# A4-B.net
KiCad netlist of a schematic drawn in Altium Designer
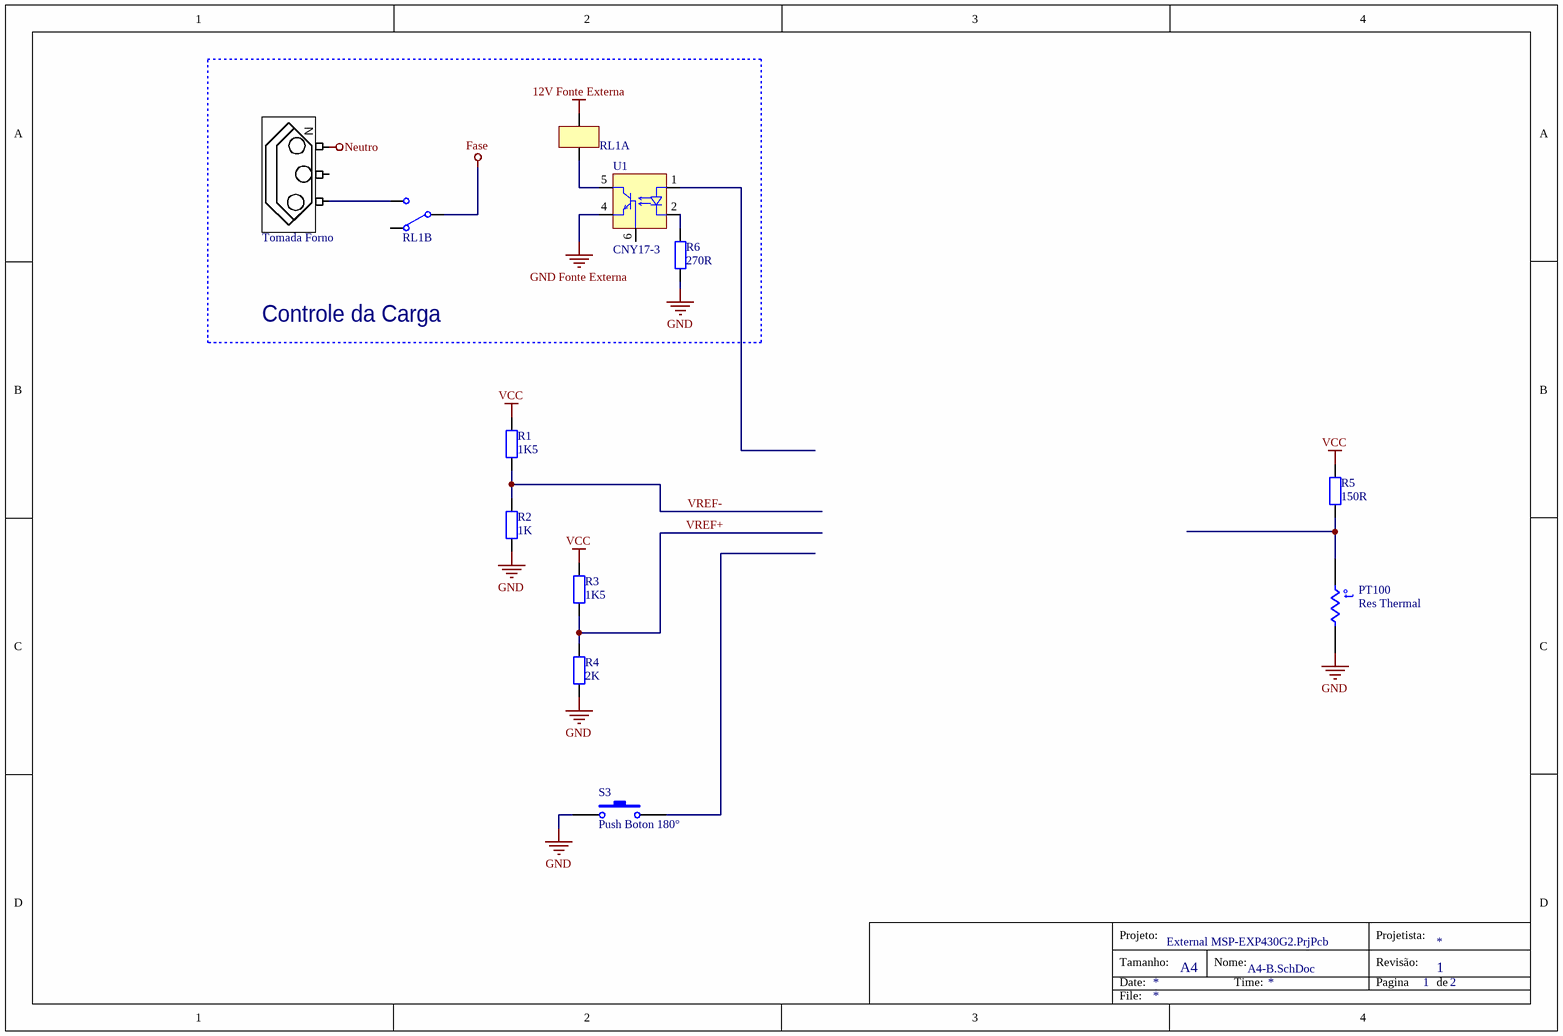
[diagram p0: A4-B.SchDoc]

(export (version "E")
  (design (tool "Eeschema 10.0.6"))
  (components
    (comp (ref "PT100")
      (value "Res Thermal")
      (footprint "6-0805_N")
      (description "Thermistor")
      (fields (field (name "PUBLISHER") "Altium Limited"))
      (libsource (lib "Miscellaneous Devices") (part "Res Thermal"))
    )
    (comp (ref "R1")
      (value "1K5")
      (footprint "Resistor 1/8")
      (description "Resistor")
      (fields (field (name "Comment") "Res 1K5") (field (name "PUBLISHER") "Altium Limited"))
      (libsource (lib "almox Gaia") (part "Res 1K5"))
    )
    (comp (ref "R2")
      (value "1K")
      (footprint "Resistor 1/8")
      (description "Resistor")
      (fields (field (name "Comment") "Res 1K") (field (name "PUBLISHER") "Altium Limited"))
      (libsource (lib "almox Gaia") (part "Res 1K"))
    )
    (comp (ref "R3")
      (value "1K5")
      (footprint "Resistor 1/8")
      (description "Resistor")
      (fields (field (name "Comment") "Res 1K5") (field (name "PUBLISHER") "Altium Limited"))
      (libsource (lib "almox Gaia") (part "Res 1K5"))
    )
    (comp (ref "R4")
      (value "2K")
      (footprint "Resistor 1/8")
      (description "Resistor")
      (fields (field (name "Comment") "Res 2K") (field (name "PUBLISHER") "Altium Limited"))
      (libsource (lib "almox Gaia") (part "Res 2K2"))
    )
    (comp (ref "R5")
      (value "150R")
      (footprint "Resistor 1/8")
      (description "Resistor")
      (fields (field (name "Comment") "Res 150R") (field (name "PUBLISHER") "Altium Limited"))
      (libsource (lib "almox Gaia") (part "Res 180R"))
    )
    (comp (ref "R6")
      (value "270R")
      (footprint "Resistor 1/8")
      (description "Resistor")
      (fields (field (name "Comment") "Res 270R") (field (name "PUBLISHER") "Altium Limited"))
      (libsource (lib "almox Gaia") (part "Res 270R"))
    )
    (comp (ref "RL1")
      (value "RELE 1NA 1NF")
      (footprint "rele SRA")
      (description "Relay")
      (fields (field (name "MANUFACTURER") "Metaltex") (field (name "PUBLISHER") "Gaia Component"))
      (libsource (lib "almox Gaia") (part "RELE 1NA 1NF"))
    )
    (comp (ref "S3")
      (value "Push Boton 180°")
      (footprint "PushButton - small - 2")
      (description "Switch")
      (fields (field (name "PUBLISHER") "Altium Limited"))
      (libsource (lib "almox Gaia") (part "Push Boton 180°"))
    )
    (comp (ref "Tomada Forno")
      (value "TOMADA AC RETA")
      (footprint "EX-1401")
      (description "TOMADA AC")
      (fields (field (name "PUBLISHER") "Altium Limited"))
      (libsource (lib "almox Gaia") (part "TOMADA AC RETA"))
    )
    (comp (ref "U1")
      (value "CNY17-3")
      (footprint "PDIP300-P6")
      (description "Optocoupler, Phototransistor Output, Dual Channel, TTL Compatible, Pb-free")
      (fields (field (name "PUBLISHER") "Altium Limited"))
      (libsource (lib "almox Gaia") (part "CNY17-3"))
    )
  )
  (nets
    (net (code "1") (name "/VREF+") (class "Default")
      (node (ref "R3") (pin "1") (pinfunction "1_1") (pintype "passive"))
      (node (ref "R4") (pin "2") (pinfunction "2_2") (pintype "passive"))
    )
    (net (code "2") (name "/VREF-") (class "Default")
      (node (ref "R1") (pin "1") (pinfunction "1_1") (pintype "passive"))
      (node (ref "R2") (pin "2") (pinfunction "2_2") (pintype "passive"))
    )
    (net (code "3") (name "12V Fonte Externa") (class "Default")
      (node (ref "RL1") (pin "1") (pinfunction "A1_1") (pintype "power_in"))
    )
    (net (code "4") (name "Fase") (class "Default")
      (node (ref "RL1") (pin "3") (pinfunction "C_3") (pintype "passive"))
    )
    (net (code "5") (name "GND") (class "Default")
      (node (ref "PT100") (pin "2") (pinfunction "2_2") (pintype "passive"))
      (node (ref "R2") (pin "1") (pinfunction "1_1") (pintype "passive"))
      (node (ref "R4") (pin "1") (pinfunction "1_1") (pintype "passive"))
      (node (ref "R6") (pin "1") (pinfunction "1_1") (pintype "passive"))
      (node (ref "S3") (pin "1") (pinfunction "1_1") (pintype "passive"))
    )
    (net (code "6") (name "GND Fonte Externa") (class "Default")
      (node (ref "U1") (pin "4") (pinfunction "E_4") (pintype "passive"))
    )
    (net (code "7") (name "Net-(PT100-Pad1)") (class "Default")
      (node (ref "PT100") (pin "1") (pinfunction "1_1") (pintype "passive"))
      (node (ref "R5") (pin "1") (pinfunction "1_1") (pintype "passive"))
    )
    (net (code "8") (name "Net-(RL1A-A2)") (class "Default")
      (node (ref "RL1") (pin "2") (pinfunction "A2_2") (pintype "power_in"))
      (node (ref "U1") (pin "5") (pinfunction "C_5") (pintype "passive"))
    )
    (net (code "9") (name "Net-(RL1B-NA)") (class "Default")
      (node (ref "RL1") (pin "5") (pinfunction "NA_5") (pintype "passive"))
      (node (ref "Tomada Forno") (pin "1") (pinfunction "F_1") (pintype "passive"))
    )
    (net (code "10") (name "Net-(U1-K)") (class "Default")
      (node (ref "R6") (pin "2") (pinfunction "2_2") (pintype "passive"))
      (node (ref "U1") (pin "2") (pinfunction "K_2") (pintype "passive"))
    )
    (net (code "11") (name "Neutro") (class "Default")
      (node (ref "Tomada Forno") (pin "3") (pinfunction "N_3") (pintype "passive"))
    )
    (net (code "12") (name "VCC") (class "Default")
      (node (ref "R1") (pin "2") (pinfunction "2_2") (pintype "passive"))
      (node (ref "R3") (pin "2") (pinfunction "2_2") (pintype "passive"))
      (node (ref "R5") (pin "2") (pinfunction "2_2") (pintype "passive"))
    )
    (net (code "13") (name "unconnected-(RL1B-NF-Pad4)") (class "Default")
      (node (ref "RL1") (pin "4") (pinfunction "NF_4") (pintype "passive"))
    )
    (net (code "14") (name "unconnected-(S3-Pad2)") (class "Default")
      (node (ref "S3") (pin "2") (pinfunction "2_2") (pintype "passive"))
    )
    (net (code "15") (name "unconnected-(Tomada Forno-T-Pad2)") (class "Default")
      (node (ref "Tomada Forno") (pin "2") (pinfunction "T_2") (pintype "passive"))
    )
    (net (code "16") (name "unconnected-(U1-A-Pad1)") (class "Default")
      (node (ref "U1") (pin "1") (pinfunction "A_1") (pintype "passive"))
    )
    (net (code "17") (name "unconnected-(U1-B-Pad6)") (class "Default")
      (node (ref "U1") (pin "6") (pinfunction "B_6") (pintype "passive"))
    )
  )
)
